# emergency.net
KiCad netlist of a schematic drawn in EAGLE
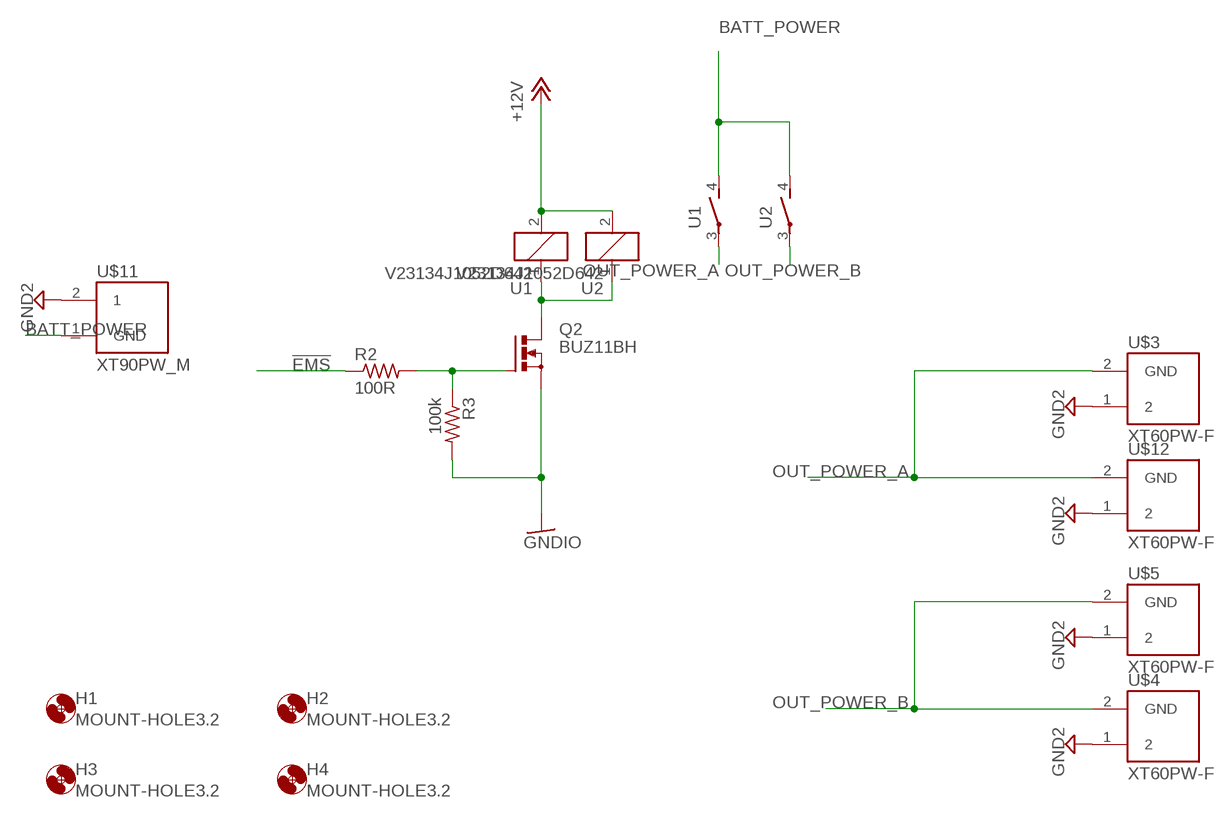
[diagram p0: schematic, sheet 1]
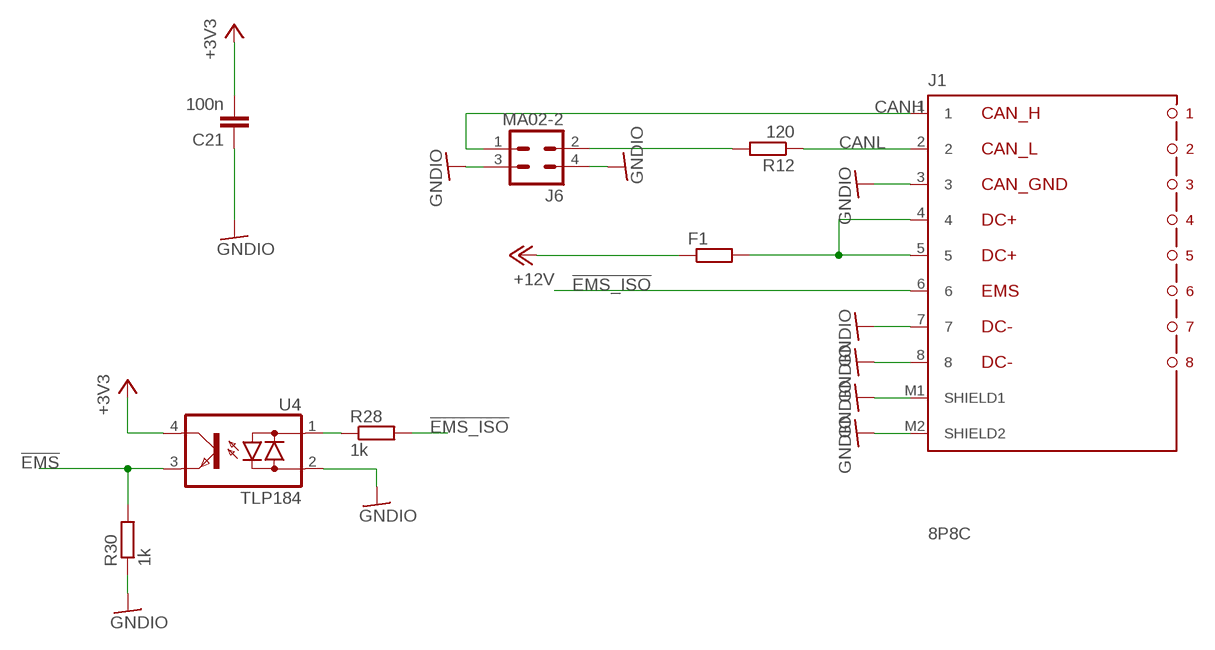
[diagram p1: schematic, sheet 2]
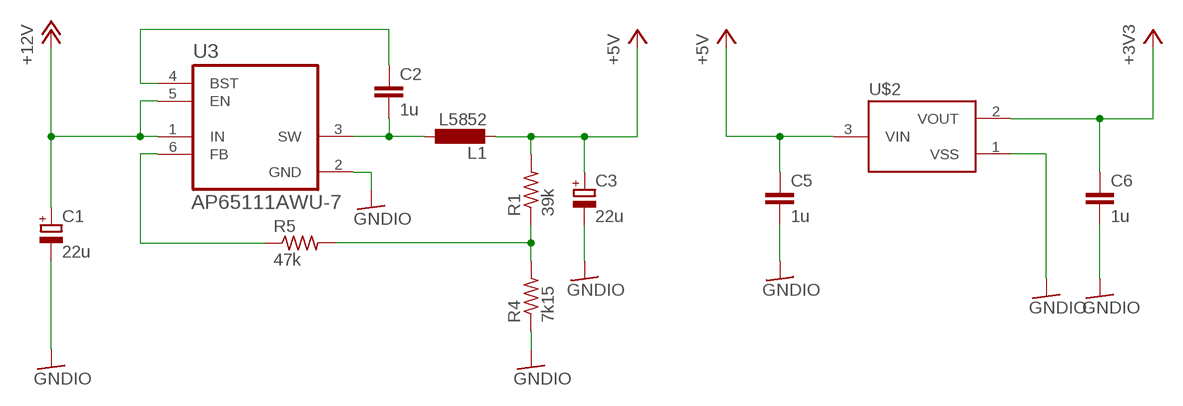
[diagram p2: schematic, sheet 3]

(export (version "E")
  (design (tool "Eeschema 10.0.6"))
  (components
    (comp (ref "C21")
      (value "100n")
      (footprint "eagle-import:C0603")
      (libsource (lib "eagle-import") (part "C-EUC0603"))
    )
    (comp (ref "F1")
      (value "R-EU_R1206")
      (footprint "eagle-import:R1206")
      (libsource (lib "eagle-import") (part "R-EU_R1206"))
    )
    (comp (ref "J1")
      (value "8P8C")
      (footprint "eagle-import:8P8C")
      (libsource (lib "eagle-import") (part "8P8C"))
    )
    (comp (ref "J6")
      (value "MA02-2")
      (footprint "eagle-import:MA02-2W")
      (libsource (lib "eagle-import") (part "MA02-2"))
    )
    (comp (ref "R12")
      (value "120")
      (footprint "eagle-import:R0603")
      (libsource (lib "eagle-import") (part "R-EU_R0603"))
    )
    (comp (ref "R28")
      (value "1k")
      (footprint "eagle-import:R0603")
      (libsource (lib "eagle-import") (part "R-EU_R0603"))
    )
    (comp (ref "R30")
      (value "1k")
      (footprint "eagle-import:R0603")
      (libsource (lib "eagle-import") (part "R-EU_R0603"))
    )
    (comp (ref "U4")
      (value "TLP184")
      (footprint "eagle-import:11-4M1S")
      (libsource (lib "eagle-import") (part "TLP184"))
    )
    (comp (ref "H1")
      (value "MOUNT-HOLE3.2")
      (footprint "eagle-import:3,2")
      (libsource (lib "eagle-import") (part "MOUNT-HOLE3.2"))
    )
    (comp (ref "H2")
      (value "MOUNT-HOLE3.2")
      (footprint "eagle-import:3,2")
      (libsource (lib "eagle-import") (part "MOUNT-HOLE3.2"))
    )
    (comp (ref "H3")
      (value "MOUNT-HOLE3.2")
      (footprint "eagle-import:3,2")
      (libsource (lib "eagle-import") (part "MOUNT-HOLE3.2"))
    )
    (comp (ref "H4")
      (value "MOUNT-HOLE3.2")
      (footprint "eagle-import:3,2")
      (libsource (lib "eagle-import") (part "MOUNT-HOLE3.2"))
    )
    (comp (ref "Q2")
      (value "BUZ11BH")
      (footprint "eagle-import:TO220BH")
      (libsource (lib "eagle-import") (part "BUZ11BH"))
    )
    (comp (ref "R2")
      (value "100R")
      (footprint "eagle-import:R0603")
      (libsource (lib "eagle-import") (part "R-US_R0603"))
    )
    (comp (ref "R3")
      (value "100k")
      (footprint "eagle-import:R0603")
      (libsource (lib "eagle-import") (part "R-US_R0603"))
    )
    (comp (ref "U$3")
      (value "XT60PW-F")
      (footprint "eagle-import:AMASS_XT60PW-F")
      (fields (field (name "MF") "AMASS") (field (name "MP") "XT60PW-M "))
      (libsource (lib "eagle-import") (part "XT60PW-F"))
    )
    (comp (ref "U$4")
      (value "XT60PW-F")
      (footprint "eagle-import:AMASS_XT60PW-F")
      (fields (field (name "MF") "AMASS") (field (name "MP") "XT60PW-M "))
      (libsource (lib "eagle-import") (part "XT60PW-F"))
    )
    (comp (ref "U$5")
      (value "XT60PW-F")
      (footprint "eagle-import:AMASS_XT60PW-F")
      (fields (field (name "MF") "AMASS") (field (name "MP") "XT60PW-M "))
      (libsource (lib "eagle-import") (part "XT60PW-F"))
    )
    (comp (ref "U$11")
      (value "XT90PW_M")
      (footprint "eagle-import:AMASS_XT90PW_M")
      (libsource (lib "eagle-import") (part "XT90PW_M"))
    )
    (comp (ref "U$12")
      (value "XT60PW-F")
      (footprint "eagle-import:AMASS_XT60PW-F")
      (fields (field (name "MF") "AMASS") (field (name "MP") "XT60PW-M "))
      (libsource (lib "eagle-import") (part "XT60PW-F"))
    )
    (comp (ref "U1")
      (value "V23134J1052D642")
      (footprint "eagle-import:V23134J1052D642")
      (libsource (lib "eagle-import") (part "V23134J1052D642"))
    )
    (comp (ref "U2")
      (value "V23134J1052D642")
      (footprint "eagle-import:V23134J1052D642")
      (libsource (lib "eagle-import") (part "V23134J1052D642"))
    )
    (comp (ref "C1")
      (value "22u")
      (footprint "eagle-import:E2-5")
      (libsource (lib "eagle-import") (part "CPOL-EUE2-5"))
    )
    (comp (ref "C2")
      (value "1u")
      (footprint "eagle-import:C0603")
      (libsource (lib "eagle-import") (part "rcl_334_C-EUC0603"))
    )
    (comp (ref "C3")
      (value "22u")
      (footprint "eagle-import:E2-5")
      (libsource (lib "eagle-import") (part "CPOL-EUE2-5"))
    )
    (comp (ref "C5")
      (value "1u")
      (footprint "eagle-import:C0603")
      (libsource (lib "eagle-import") (part "rcl_334_C-EUC0603"))
    )
    (comp (ref "C6")
      (value "1u")
      (footprint "eagle-import:C0603")
      (libsource (lib "eagle-import") (part "rcl_334_C-EUC0603"))
    )
    (comp (ref "L1")
      (value "L5852")
      (footprint "eagle-import:L5852")
      (libsource (lib "eagle-import") (part "L5852"))
    )
    (comp (ref "R1")
      (value "39k")
      (footprint "eagle-import:R0603")
      (libsource (lib "eagle-import") (part "R-US_R0603"))
    )
    (comp (ref "R4")
      (value "7k15")
      (footprint "eagle-import:R0603")
      (libsource (lib "eagle-import") (part "R-US_R0603"))
    )
    (comp (ref "R5")
      (value "47k")
      (footprint "eagle-import:R0603")
      (libsource (lib "eagle-import") (part "R-US_R0603"))
    )
    (comp (ref "U$2")
      (value "AP2120")
      (footprint "eagle-import:SOT95P240X110-3")
      (libsource (lib "eagle-import") (part "AP2120"))
    )
    (comp (ref "U3")
      (value "AP65111AWU-7")
      (footprint "eagle-import:SOT95P280X100-6N")
      (fields (field (name "DIGI-KEY_PART_NUMBER") "AP65111AWU-7DICT-ND") (field (name "MF") "Diodes Inc."))
      (libsource (lib "eagle-import") (part "AP65111AWU-7"))
    )
  )
  (nets
    (net (code "1") (name "+3V3") (class "Default")
      (node (ref "C21") (pin "2") (pinfunction "2_2") (pintype "passive"))
      (node (ref "C6") (pin "1") (pinfunction "1_1") (pintype "passive"))
      (node (ref "U$2") (pin "2") (pinfunction "VOUT_2") (pintype "bidirectional"))
      (node (ref "U4") (pin "4") (pinfunction "C_4") (pintype "passive"))
    )
    (net (code "2") (name "+5V") (class "Default")
      (node (ref "C3") (pin "+") (pinfunction "+_+") (pintype "passive"))
      (node (ref "C5") (pin "1") (pinfunction "1_1") (pintype "passive"))
      (node (ref "L1") (pin "P$2") (pinfunction "2_P$2") (pintype "passive"))
      (node (ref "R1") (pin "2") (pinfunction "2_2") (pintype "passive"))
      (node (ref "U$2") (pin "3") (pinfunction "VIN_3") (pintype "bidirectional"))
    )
    (net (code "3") (name "+12V") (class "Default")
      (node (ref "C1") (pin "+") (pinfunction "+_+") (pintype "passive"))
      (node (ref "F1") (pin "1") (pinfunction "1_1") (pintype "passive"))
      (node (ref "U1") (pin "2") (pinfunction "2_2") (pintype "passive"))
      (node (ref "U2") (pin "2") (pinfunction "2_2") (pintype "passive"))
      (node (ref "U3") (pin "1") (pinfunction "IN_1") (pintype "input"))
      (node (ref "U3") (pin "5") (pinfunction "EN_5") (pintype "input"))
    )
    (net (code "4") (name "BATT_POWER") (class "Default")
      (node (ref "U$11") (pin "1") (pinfunction "GND_1") (pintype "passive"))
      (node (ref "U1") (pin "4") (pinfunction "S_4") (pintype "passive"))
      (node (ref "U2") (pin "4") (pinfunction "S_4") (pintype "passive"))
    )
    (net (code "5") (name "CANH") (class "Default")
      (node (ref "J1") (pin "1") (pinfunction "1_1") (pintype "input"))
      (node (ref "J6") (pin "1") (pinfunction "1_1") (pintype "passive"))
    )
    (net (code "6") (name "CANL") (class "Default")
      (node (ref "J1") (pin "2") (pinfunction "2_2") (pintype "input"))
      (node (ref "R12") (pin "1") (pinfunction "1_1") (pintype "passive"))
    )
    (net (code "7") (name "GND2") (class "Default")
      (node (ref "U$11") (pin "2") (pinfunction "1_2") (pintype "passive"))
      (node (ref "U$12") (pin "1") (pinfunction "2_1") (pintype "passive"))
      (node (ref "U$3") (pin "1") (pinfunction "2_1") (pintype "passive"))
      (node (ref "U$4") (pin "1") (pinfunction "2_1") (pintype "passive"))
      (node (ref "U$5") (pin "1") (pinfunction "2_1") (pintype "passive"))
    )
    (net (code "8") (name "GNDIO") (class "Default")
      (node (ref "C1") (pin "-") (pinfunction "-_-") (pintype "passive"))
      (node (ref "C21") (pin "1") (pinfunction "1_1") (pintype "passive"))
      (node (ref "C3") (pin "-") (pinfunction "-_-") (pintype "passive"))
      (node (ref "C5") (pin "2") (pinfunction "2_2") (pintype "passive"))
      (node (ref "C6") (pin "2") (pinfunction "2_2") (pintype "passive"))
      (node (ref "J1") (pin "3") (pinfunction "3_3") (pintype "input"))
      (node (ref "J1") (pin "7") (pinfunction "7_7") (pintype "input"))
      (node (ref "J1") (pin "8") (pinfunction "8_8") (pintype "input"))
      (node (ref "J1") (pin "M1") (pinfunction "SHIELD1_M1") (pintype "passive"))
      (node (ref "J1") (pin "M2") (pinfunction "SHIELD2_M2") (pintype "passive"))
      (node (ref "J6") (pin "3") (pinfunction "3_3") (pintype "passive"))
      (node (ref "J6") (pin "4") (pinfunction "4_4") (pintype "passive"))
      (node (ref "Q2") (pin "S") (pinfunction "S_S") (pintype "passive"))
      (node (ref "R3") (pin "2") (pinfunction "2_2") (pintype "passive"))
      (node (ref "R30") (pin "1") (pinfunction "1_1") (pintype "passive"))
      (node (ref "R4") (pin "1") (pinfunction "1_1") (pintype "passive"))
      (node (ref "U$2") (pin "1") (pinfunction "VSS_1") (pintype "bidirectional"))
      (node (ref "U3") (pin "2") (pinfunction "GND_2") (pintype "power_in"))
      (node (ref "U4") (pin "2") (pinfunction "AC2_2") (pintype "passive"))
    )
    (net (code "9") (name "Net-(F1-Pad2)") (class "Default")
      (node (ref "F1") (pin "2") (pinfunction "2_2") (pintype "passive"))
      (node (ref "J1") (pin "4") (pinfunction "4_4") (pintype "input"))
      (node (ref "J1") (pin "5") (pinfunction "5_5") (pintype "input"))
    )
    (net (code "10") (name "Net-(J6-Pad2)") (class "Default")
      (node (ref "J6") (pin "2") (pinfunction "2_2") (pintype "passive"))
      (node (ref "R12") (pin "2") (pinfunction "2_2") (pintype "passive"))
    )
    (net (code "11") (name "Net-(L1-1)") (class "Default")
      (node (ref "C2") (pin "2") (pinfunction "2_2") (pintype "passive"))
      (node (ref "L1") (pin "P$1") (pinfunction "1_P$1") (pintype "passive"))
      (node (ref "U3") (pin "3") (pinfunction "SW_3") (pintype "output"))
    )
    (net (code "12") (name "Net-(Q2-PadD)") (class "Default")
      (node (ref "Q2") (pin "D") (pinfunction "D_D") (pintype "passive"))
      (node (ref "U1") (pin "1") (pinfunction "1_1") (pintype "passive"))
      (node (ref "U2") (pin "1") (pinfunction "1_1") (pintype "passive"))
    )
    (net (code "13") (name "Net-(Q2-PadG)") (class "Default")
      (node (ref "Q2") (pin "G") (pinfunction "G_G") (pintype "passive"))
      (node (ref "R2") (pin "2") (pinfunction "2_2") (pintype "passive"))
      (node (ref "R3") (pin "1") (pinfunction "1_1") (pintype "passive"))
    )
    (net (code "14") (name "Net-(R1-Pad1)") (class "Default")
      (node (ref "R1") (pin "1") (pinfunction "1_1") (pintype "passive"))
      (node (ref "R4") (pin "2") (pinfunction "2_2") (pintype "passive"))
      (node (ref "R5") (pin "2") (pinfunction "2_2") (pintype "passive"))
    )
    (net (code "15") (name "Net-(U3-BST)") (class "Default")
      (node (ref "C2") (pin "1") (pinfunction "1_1") (pintype "passive"))
      (node (ref "U3") (pin "4") (pinfunction "BST_4") (pintype "input"))
    )
    (net (code "16") (name "Net-(U3-FB)") (class "Default")
      (node (ref "R5") (pin "1") (pinfunction "1_1") (pintype "passive"))
      (node (ref "U3") (pin "6") (pinfunction "FB_6") (pintype "input"))
    )
    (net (code "17") (name "Net-(U4-AC1)") (class "Default")
      (node (ref "R28") (pin "1") (pinfunction "1_1") (pintype "passive"))
      (node (ref "U4") (pin "1") (pinfunction "AC1_1") (pintype "passive"))
    )
    (net (code "18") (name "OUT_POWER_A") (class "Default")
      (node (ref "U$12") (pin "2") (pinfunction "GND_2") (pintype "passive"))
      (node (ref "U$3") (pin "2") (pinfunction "GND_2") (pintype "passive"))
      (node (ref "U1") (pin "3") (pinfunction "P_3") (pintype "passive"))
    )
    (net (code "19") (name "OUT_POWER_B") (class "Default")
      (node (ref "U$4") (pin "2") (pinfunction "GND_2") (pintype "passive"))
      (node (ref "U$5") (pin "2") (pinfunction "GND_2") (pintype "passive"))
      (node (ref "U2") (pin "3") (pinfunction "P_3") (pintype "passive"))
    )
    (net (code "20") (name "~{EMS_ISO}") (class "Default")
      (node (ref "J1") (pin "6") (pinfunction "6_6") (pintype "input"))
      (node (ref "R28") (pin "2") (pinfunction "2_2") (pintype "passive"))
    )
    (net (code "21") (name "~{EMS}") (class "Default")
      (node (ref "R2") (pin "1") (pinfunction "1_1") (pintype "passive"))
      (node (ref "R30") (pin "2") (pinfunction "2_2") (pintype "passive"))
      (node (ref "U4") (pin "3") (pinfunction "E_3") (pintype "passive"))
    )
  )
)
